# Sheet2.net
KiCad netlist of a schematic drawn in Altium Designer
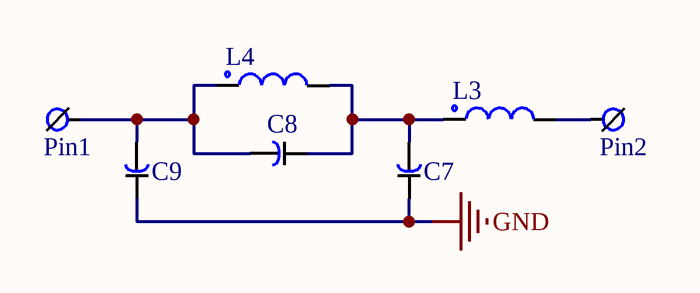
[diagram p0: Sheet2.SchDoc]

(export (version "E")
  (design (tool "Eeschema 10.0.6"))
  (components
    (comp (ref "C7") (value "C7") (footprint "C7(1206)") (libsource (lib "Schlib") (part "C7")))
    (comp (ref "C8") (value "C8") (footprint "C8(1812)") (libsource (lib "Schlib") (part "C8")))
    (comp (ref "C9") (value "C9") (footprint "C9(1812)") (libsource (lib "Schlib") (part "C9")))
    (comp (ref "L3") (value "L") (footprint "L3,L4") (libsource (lib "Schlib") (part "L")))
    (comp (ref "L4") (value "L") (footprint "L3,L4") (libsource (lib "Schlib") (part "L")))
    (comp (ref "Pin1") (value "Pin") (footprint "Pin") (libsource (lib "Schlib") (part "Pin")))
    (comp (ref "Pin2") (value "Pin") (footprint "Pin") (libsource (lib "Schlib") (part "Pin")))
  )
  (nets
    (net (code "1") (name "GND") (class "Default")
      (node (ref "C7") (pin "2") (pinfunction "2_2") (pintype "passive"))
      (node (ref "C9") (pin "2") (pinfunction "2_2") (pintype "passive"))
    )
    (net (code "2") (name "Net-(C7-Pad1)") (class "Default")
      (node (ref "C7") (pin "1") (pinfunction "1_1") (pintype "passive"))
      (node (ref "C8") (pin "2") (pinfunction "2_2") (pintype "passive"))
      (node (ref "L3") (pin "1") (pinfunction "1_1") (pintype "passive"))
      (node (ref "L4") (pin "2") (pinfunction "2_2") (pintype "passive"))
    )
    (net (code "3") (name "Net-(Pin1-4)") (class "Default")
      (node (ref "C8") (pin "1") (pinfunction "1_1") (pintype "passive"))
      (node (ref "C9") (pin "1") (pinfunction "1_1") (pintype "passive"))
      (node (ref "L4") (pin "1") (pinfunction "1_1") (pintype "passive"))
      (node (ref "Pin1") (pin "1") (pinfunction "4_1") (pintype "passive"))
    )
    (net (code "4") (name "Net-(Pin2-4)") (class "Default")
      (node (ref "L3") (pin "2") (pinfunction "2_2") (pintype "passive"))
      (node (ref "Pin2") (pin "1") (pinfunction "4_1") (pintype "passive"))
    )
  )
)
